# dragonite.net
KiCad netlist of a schematic drawn in EAGLE
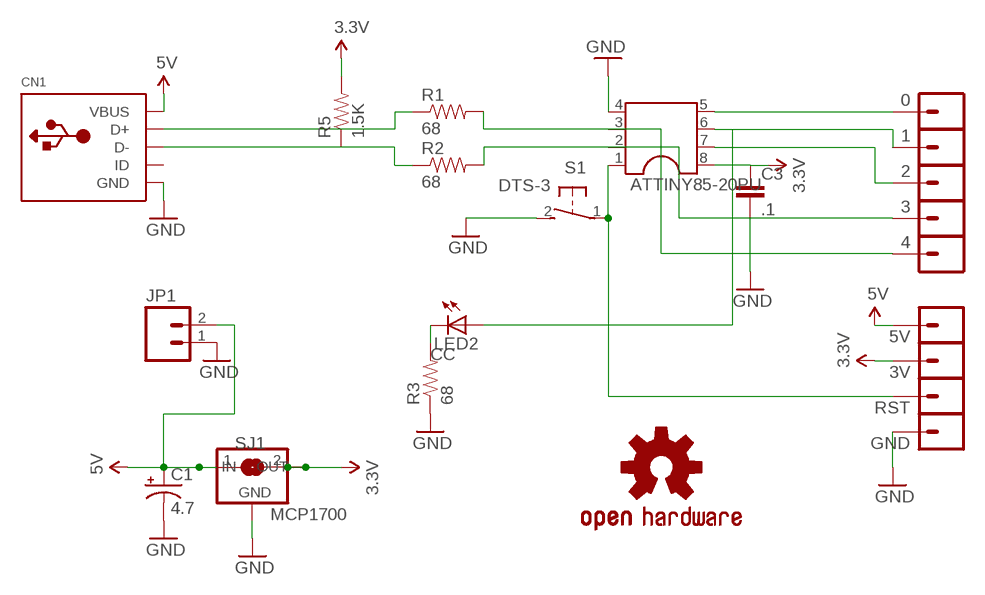
[diagram p0: schematic, sheet 1]

(export (version "E")
  (design (tool "Eeschema 10.0.6"))
  (components
    (comp (ref "0")
      (value "M01SMDNS")
      (footprint "eagle-import:1X01NS")
      (libsource (lib "eagle-import") (part "M01SMDNS"))
    )
    (comp (ref "1")
      (value "M01SMDNS")
      (footprint "eagle-import:1X01NS")
      (libsource (lib "eagle-import") (part "M01SMDNS"))
    )
    (comp (ref "2")
      (value "M01SMDNS")
      (footprint "eagle-import:1X01NS")
      (libsource (lib "eagle-import") (part "M01SMDNS"))
    )
    (comp (ref "3")
      (value "M01SMDNS")
      (footprint "eagle-import:1X01NS")
      (libsource (lib "eagle-import") (part "M01SMDNS"))
    )
    (comp (ref "3V")
      (value "M01SMDNS")
      (footprint "eagle-import:1X01NS")
      (libsource (lib "eagle-import") (part "M01SMDNS"))
    )
    (comp (ref "4")
      (value "M01SMDNS")
      (footprint "eagle-import:1X01NS")
      (libsource (lib "eagle-import") (part "M01SMDNS"))
    )
    (comp (ref "5V")
      (value "M01SMDNS")
      (footprint "eagle-import:1X01NS")
      (libsource (lib "eagle-import") (part "M01SMDNS"))
    )
    (comp (ref "ATTINY85-20PU")
      (value "DIL8")
      (footprint "eagle-import:DIL08")
      (libsource (lib "eagle-import") (part "DIL8"))
    )
    (comp (ref "C1")
      (value "4.7")
      (footprint "eagle-import:E2-4")
      (libsource (lib "eagle-import") (part "CPOL-USE2-4"))
    )
    (comp (ref "C3")
      (value ".1")
      (footprint "eagle-import:CAP-PTH-SMALLEZ")
      (libsource (lib "eagle-import") (part "CAPEZ"))
    )
    (comp (ref "CN1")
      (value "USBMOLEX")
      (footprint "eagle-import:USB-MINIB-THM-MOLEX")
      (libsource (lib "eagle-import") (part "USBMOLEX"))
    )
    (comp (ref "GND")
      (value "M01SMDNS")
      (footprint "eagle-import:1X01NS")
      (libsource (lib "eagle-import") (part "M01SMDNS"))
    )
    (comp (ref "JP1")
      (value "M02JST-PTH-2")
      (footprint "eagle-import:JST-2-PTH")
      (libsource (lib "eagle-import") (part "M02JST-PTH-2"))
    )
    (comp (ref "LED2")
      (value "LED3MM")
      (footprint "eagle-import:LED3MM")
      (libsource (lib "eagle-import") (part "LED3MM"))
    )
    (comp (ref "MCP1700")
      (value "V_REG_78XXTO-92")
      (footprint "eagle-import:TO-92")
      (libsource (lib "eagle-import") (part "V_REG_78XXTO-92"))
    )
    (comp (ref "R1")
      (value "68")
      (footprint "eagle-import:1_6W-RES")
      (libsource (lib "eagle-import") (part "RESISTORPTH-1/6W"))
    )
    (comp (ref "R2")
      (value "68")
      (footprint "eagle-import:1_6W-RES")
      (libsource (lib "eagle-import") (part "RESISTORPTH-1/6W"))
    )
    (comp (ref "R3")
      (value "68")
      (footprint "eagle-import:1_6W-RES")
      (libsource (lib "eagle-import") (part "RESISTORPTH-1/6W"))
    )
    (comp (ref "R5")
      (value "1.5K")
      (footprint "eagle-import:1_6W-RES")
      (libsource (lib "eagle-import") (part "RESISTORPTH-1/6W"))
    )
    (comp (ref "RST")
      (value "M01SMDNS")
      (footprint "eagle-import:1X01NS")
      (libsource (lib "eagle-import") (part "M01SMDNS"))
    )
    (comp (ref "S1")
      (value "DTS-3")
      (footprint "eagle-import:DTS-3")
      (libsource (lib "eagle-import") (part "DTS-3"))
    )
    (comp (ref "SJ1")
      (value "JUMPER_SJSJ_SMALLER")
      (footprint "eagle-import:JUMPER_SJ_1_SMALLER")
      (libsource (lib "eagle-import") (part "JUMPER_SJSJ_SMALLER"))
    )
    (comp (ref "U$4")
      (value "OSHW-LOGOS")
      (footprint "eagle-import:OSHW-LOGO-S")
      (libsource (lib "eagle-import") (part "OSHW-LOGOS"))
    )
  )
  (nets
    (net (code "1") (name "3.3V") (class "Default")
      (node (ref "3V") (pin "1") (pinfunction "1_1") (pintype "passive"))
      (node (ref "ATTINY85-20PU") (pin "8") (pinfunction "8_8") (pintype "passive"))
      (node (ref "C3") (pin "1") (pinfunction "1_1") (pintype "passive"))
      (node (ref "MCP1700") (pin "3") (pinfunction "OUT_3") (pintype "power_in"))
      (node (ref "R5") (pin "2") (pinfunction "2_2") (pintype "passive"))
      (node (ref "SJ1") (pin "2") (pinfunction "2_2") (pintype "passive"))
    )
    (net (code "2") (name "5V") (class "Default")
      (node (ref "5V") (pin "1") (pinfunction "1_1") (pintype "passive"))
      (node (ref "C1") (pin "+") (pinfunction "+_+") (pintype "passive"))
      (node (ref "CN1") (pin "VBUS") (pinfunction "VBUS_VBUS") (pintype "power_in"))
      (node (ref "JP1") (pin "2") (pinfunction "2_2") (pintype "passive"))
      (node (ref "MCP1700") (pin "2") (pinfunction "IN_2") (pintype "input"))
      (node (ref "SJ1") (pin "1") (pinfunction "1_1") (pintype "passive"))
    )
    (net (code "3") (name "GND") (class "Default")
      (node (ref "ATTINY85-20PU") (pin "4") (pinfunction "4_4") (pintype "passive"))
      (node (ref "C1") (pin "-") (pinfunction "-_-") (pintype "passive"))
      (node (ref "C3") (pin "2") (pinfunction "2_2") (pintype "passive"))
      (node (ref "CN1") (pin "GND") (pinfunction "GND_GND") (pintype "power_in"))
      (node (ref "GND") (pin "1") (pinfunction "1_1") (pintype "passive"))
      (node (ref "JP1") (pin "1") (pinfunction "1_1") (pintype "passive"))
      (node (ref "MCP1700") (pin "1") (pinfunction "GND_1") (pintype "power_in"))
      (node (ref "R3") (pin "1") (pinfunction "1_1") (pintype "passive"))
      (node (ref "S1") (pin "2") (pinfunction "2_2") (pintype "passive"))
    )
    (net (code "4") (name "Net-(0-Pad1)") (class "Default")
      (node (ref "0") (pin "1") (pinfunction "1_1") (pintype "passive"))
      (node (ref "ATTINY85-20PU") (pin "5") (pinfunction "5_5") (pintype "passive"))
    )
    (net (code "5") (name "Net-(1-Pad1)") (class "Default")
      (node (ref "1") (pin "1") (pinfunction "1_1") (pintype "passive"))
      (node (ref "ATTINY85-20PU") (pin "6") (pinfunction "6_6") (pintype "passive"))
      (node (ref "LED2") (pin "A") (pinfunction "A_A") (pintype "passive"))
    )
    (net (code "6") (name "Net-(2-Pad1)") (class "Default")
      (node (ref "2") (pin "1") (pinfunction "1_1") (pintype "passive"))
      (node (ref "ATTINY85-20PU") (pin "7") (pinfunction "7_7") (pintype "passive"))
    )
    (net (code "7") (name "Net-(3-Pad1)") (class "Default")
      (node (ref "3") (pin "1") (pinfunction "1_1") (pintype "passive"))
      (node (ref "ATTINY85-20PU") (pin "2") (pinfunction "2_2") (pintype "passive"))
      (node (ref "R2") (pin "2") (pinfunction "2_2") (pintype "passive"))
    )
    (net (code "8") (name "Net-(4-Pad1)") (class "Default")
      (node (ref "4") (pin "1") (pinfunction "1_1") (pintype "passive"))
      (node (ref "ATTINY85-20PU") (pin "3") (pinfunction "3_3") (pintype "passive"))
      (node (ref "R1") (pin "2") (pinfunction "2_2") (pintype "passive"))
    )
    (net (code "9") (name "Net-(ATTINY85-20PU-Pad1)") (class "Default")
      (node (ref "ATTINY85-20PU") (pin "1") (pinfunction "1_1") (pintype "passive"))
      (node (ref "RST") (pin "1") (pinfunction "1_1") (pintype "passive"))
      (node (ref "S1") (pin "1") (pinfunction "1_1") (pintype "passive"))
    )
    (net (code "10") (name "Net-(CN1-PadD+)") (class "Default")
      (node (ref "CN1") (pin "D+") (pinfunction "D+_D+") (pintype "bidirectional"))
      (node (ref "R1") (pin "1") (pinfunction "1_1") (pintype "passive"))
    )
    (net (code "11") (name "Net-(CN1-PadD-)") (class "Default")
      (node (ref "CN1") (pin "D-") (pinfunction "D-_D-") (pintype "bidirectional"))
      (node (ref "R2") (pin "1") (pinfunction "1_1") (pintype "passive"))
      (node (ref "R5") (pin "1") (pinfunction "1_1") (pintype "passive"))
    )
    (net (code "12") (name "Net-(LED2-C)") (class "Default")
      (node (ref "LED2") (pin "K") (pinfunction "C_K") (pintype "passive"))
      (node (ref "R3") (pin "2") (pinfunction "2_2") (pintype "passive"))
    )
    (net (code "13") (name "unconnected-(CN1-PadID)") (class "Default")
      (node (ref "CN1") (pin "ID") (pinfunction "ID_ID") (pintype "bidirectional"))
    )
  )
)
